# vericishcmtc.net
KiCad netlist of a schematic drawn in EAGLE
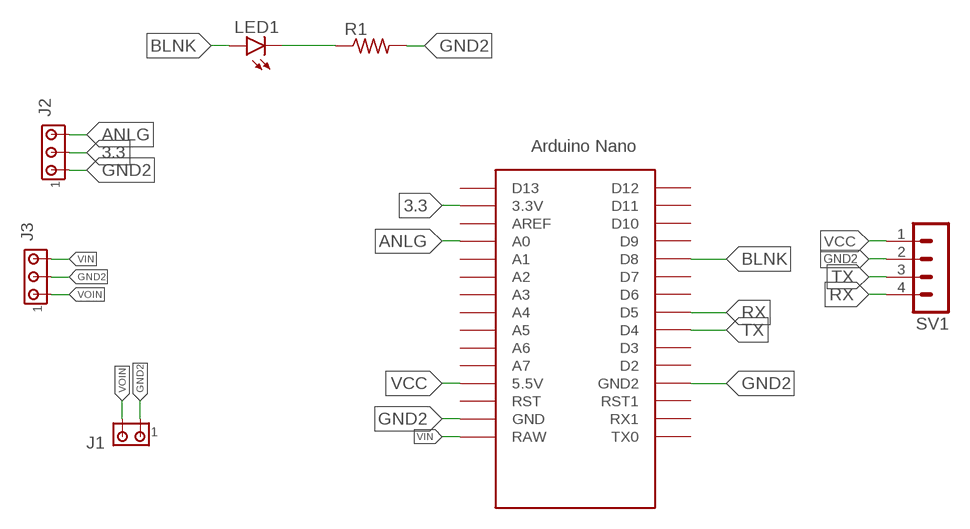
[diagram p0: schematic, sheet 1]

(export (version "E")
  (design (tool "Eeschema 10.0.6"))
  (components
    (comp (ref "J1")
      (value "MTA02-100")
      (footprint "eagle-import:10X02MTA")
      (libsource (lib "eagle-import") (part "MTA02-100"))
    )
    (comp (ref "J2")
      (value "MTA03-100")
      (footprint "eagle-import:10X03MTA")
      (libsource (lib "eagle-import") (part "MTA03-100"))
    )
    (comp (ref "J3")
      (value "MTA03-100")
      (footprint "eagle-import:10X03MTA")
      (libsource (lib "eagle-import") (part "MTA03-100"))
    )
    (comp (ref "LED1")
      (value "LED5MM")
      (footprint "eagle-import:LED5MM")
      (libsource (lib "eagle-import") (part "LED5MM"))
    )
    (comp (ref "R1")
      (value "R-US_0204/5")
      (footprint "eagle-import:0204_5")
      (libsource (lib "eagle-import") (part "R-US_0204/5"))
    )
    (comp (ref "SV1")
      (value "MA04-1")
      (footprint "eagle-import:MA04-1")
      (libsource (lib "eagle-import") (part "MA04-1"))
    )
    (comp (ref "U$1")
      (value "NANO")
      (footprint "eagle-import:NANO")
      (libsource (lib "eagle-import") (part "NANO"))
    )
  )
  (nets
    (net (code "1") (name "3.3") (class "Default")
      (node (ref "J2") (pin "2") (pinfunction "2_2") (pintype "passive"))
      (node (ref "U$1") (pin "3.3V") (pinfunction "3.3V_3.3V") (pintype "bidirectional"))
    )
    (net (code "2") (name "ANLG") (class "Default")
      (node (ref "J2") (pin "3") (pinfunction "3_3") (pintype "passive"))
      (node (ref "U$1") (pin "A0") (pinfunction "A0_A0") (pintype "bidirectional"))
    )
    (net (code "3") (name "BLNK") (class "Default")
      (node (ref "LED1") (pin "A") (pinfunction "A_A") (pintype "passive"))
      (node (ref "U$1") (pin "D8") (pinfunction "D8_D8") (pintype "bidirectional"))
    )
    (net (code "4") (name "GND2") (class "Default")
      (node (ref "J1") (pin "1") (pinfunction "1_1") (pintype "passive"))
      (node (ref "J2") (pin "1") (pinfunction "1_1") (pintype "passive"))
      (node (ref "J3") (pin "2") (pinfunction "2_2") (pintype "passive"))
      (node (ref "R1") (pin "2") (pinfunction "2_2") (pintype "passive"))
      (node (ref "SV1") (pin "2") (pinfunction "2_2") (pintype "passive"))
      (node (ref "U$1") (pin "GND") (pinfunction "GND_GND") (pintype "bidirectional"))
      (node (ref "U$1") (pin "GND1") (pinfunction "GND2_GND1") (pintype "bidirectional"))
    )
    (net (code "5") (name "Net-(LED1-C)") (class "Default")
      (node (ref "LED1") (pin "K") (pinfunction "C_K") (pintype "passive"))
      (node (ref "R1") (pin "1") (pinfunction "1_1") (pintype "passive"))
    )
    (net (code "6") (name "RX") (class "Default")
      (node (ref "SV1") (pin "4") (pinfunction "4_4") (pintype "passive"))
      (node (ref "U$1") (pin "D5") (pinfunction "D5_D5") (pintype "bidirectional"))
    )
    (net (code "7") (name "TX") (class "Default")
      (node (ref "SV1") (pin "3") (pinfunction "3_3") (pintype "passive"))
      (node (ref "U$1") (pin "D4") (pinfunction "D4_D4") (pintype "bidirectional"))
    )
    (net (code "8") (name "VCC") (class "Default")
      (node (ref "SV1") (pin "1") (pinfunction "1_1") (pintype "passive"))
      (node (ref "U$1") (pin "5V") (pinfunction "5.5V_5V") (pintype "bidirectional"))
    )
    (net (code "9") (name "VIN") (class "Default")
      (node (ref "J3") (pin "3") (pinfunction "3_3") (pintype "passive"))
      (node (ref "U$1") (pin "RAW") (pinfunction "RAW_RAW") (pintype "bidirectional"))
    )
    (net (code "10") (name "VOIN") (class "Default")
      (node (ref "J1") (pin "2") (pinfunction "2_2") (pintype "passive"))
      (node (ref "J3") (pin "1") (pinfunction "1_1") (pintype "passive"))
    )
    (net (code "11") (name "unconnected-(U$1-PadA1)") (class "Default")
      (node (ref "U$1") (pin "A1") (pinfunction "A1_A1") (pintype "bidirectional"))
    )
    (net (code "12") (name "unconnected-(U$1-PadA2)") (class "Default")
      (node (ref "U$1") (pin "A2") (pinfunction "A2_A2") (pintype "bidirectional"))
    )
    (net (code "13") (name "unconnected-(U$1-PadA3)") (class "Default")
      (node (ref "U$1") (pin "A3") (pinfunction "A3_A3") (pintype "bidirectional"))
    )
    (net (code "14") (name "unconnected-(U$1-PadA4)") (class "Default")
      (node (ref "U$1") (pin "A4") (pinfunction "A4_A4") (pintype "bidirectional"))
    )
    (net (code "15") (name "unconnected-(U$1-PadA5)") (class "Default")
      (node (ref "U$1") (pin "A5") (pinfunction "A5_A5") (pintype "bidirectional"))
    )
    (net (code "16") (name "unconnected-(U$1-PadA6)") (class "Default")
      (node (ref "U$1") (pin "A6") (pinfunction "A6_A6") (pintype "bidirectional"))
    )
    (net (code "17") (name "unconnected-(U$1-PadA7)") (class "Default")
      (node (ref "U$1") (pin "A7") (pinfunction "A7_A7") (pintype "bidirectional"))
    )
    (net (code "18") (name "unconnected-(U$1-PadAREF)") (class "Default")
      (node (ref "U$1") (pin "AREF") (pinfunction "AREF_AREF") (pintype "bidirectional"))
    )
    (net (code "19") (name "unconnected-(U$1-PadD2)") (class "Default")
      (node (ref "U$1") (pin "D2") (pinfunction "D2_D2") (pintype "bidirectional"))
    )
    (net (code "20") (name "unconnected-(U$1-PadD3)") (class "Default")
      (node (ref "U$1") (pin "D3") (pinfunction "D3_D3") (pintype "bidirectional"))
    )
    (net (code "21") (name "unconnected-(U$1-PadD6)") (class "Default")
      (node (ref "U$1") (pin "D6") (pinfunction "D6_D6") (pintype "bidirectional"))
    )
    (net (code "22") (name "unconnected-(U$1-PadD7)") (class "Default")
      (node (ref "U$1") (pin "D7") (pinfunction "D7_D7") (pintype "bidirectional"))
    )
    (net (code "23") (name "unconnected-(U$1-PadD9)") (class "Default")
      (node (ref "U$1") (pin "D9") (pinfunction "D9_D9") (pintype "bidirectional"))
    )
    (net (code "24") (name "unconnected-(U$1-PadD10)") (class "Default")
      (node (ref "U$1") (pin "D10") (pinfunction "D10_D10") (pintype "bidirectional"))
    )
    (net (code "25") (name "unconnected-(U$1-PadD11)") (class "Default")
      (node (ref "U$1") (pin "D11") (pinfunction "D11_D11") (pintype "bidirectional"))
    )
    (net (code "26") (name "unconnected-(U$1-PadD12)") (class "Default")
      (node (ref "U$1") (pin "D12") (pinfunction "D12_D12") (pintype "bidirectional"))
    )
    (net (code "27") (name "unconnected-(U$1-PadD13)") (class "Default")
      (node (ref "U$1") (pin "D13") (pinfunction "D13_D13") (pintype "bidirectional"))
    )
    (net (code "28") (name "unconnected-(U$1-PadICSP1)") (class "Default")
      (node (ref "U$1") (pin "ICSP1") (pinfunction "ICSP1_ICSP1") (pintype "bidirectional"))
    )
    (net (code "29") (name "unconnected-(U$1-PadICSP2)") (class "Default")
      (node (ref "U$1") (pin "ICSP2") (pinfunction "ICSP2_ICSP2") (pintype "bidirectional"))
    )
    (net (code "30") (name "unconnected-(U$1-PadICSP3)") (class "Default")
      (node (ref "U$1") (pin "ICSP3") (pinfunction "ICSP3_ICSP3") (pintype "bidirectional"))
    )
    (net (code "31") (name "unconnected-(U$1-PadICSP4)") (class "Default")
      (node (ref "U$1") (pin "ICSP4") (pinfunction "ICSP4_ICSP4") (pintype "bidirectional"))
    )
    (net (code "32") (name "unconnected-(U$1-PadICSP5)") (class "Default")
      (node (ref "U$1") (pin "ICSP5") (pinfunction "ICSP5_ICSP5") (pintype "bidirectional"))
    )
    (net (code "33") (name "unconnected-(U$1-PadICSP6)") (class "Default")
      (node (ref "U$1") (pin "ICSP6") (pinfunction "ICSP6_ICSP6") (pintype "bidirectional"))
    )
    (net (code "34") (name "unconnected-(U$1-PadRST)") (class "Default")
      (node (ref "U$1") (pin "RST") (pinfunction "RST_RST") (pintype "bidirectional"))
    )
    (net (code "35") (name "unconnected-(U$1-PadRST1)") (class "Default")
      (node (ref "U$1") (pin "RST1") (pinfunction "RST1_RST1") (pintype "bidirectional"))
    )
    (net (code "36") (name "unconnected-(U$1-PadRX1)") (class "Default")
      (node (ref "U$1") (pin "RX1") (pinfunction "RX1_RX1") (pintype "bidirectional"))
    )
    (net (code "37") (name "unconnected-(U$1-PadTX0)") (class "Default")
      (node (ref "U$1") (pin "TX0") (pinfunction "TX0_TX0") (pintype "bidirectional"))
    )
  )
)
